# LCD.net
KiCad netlist of a schematic drawn in Altium Designer
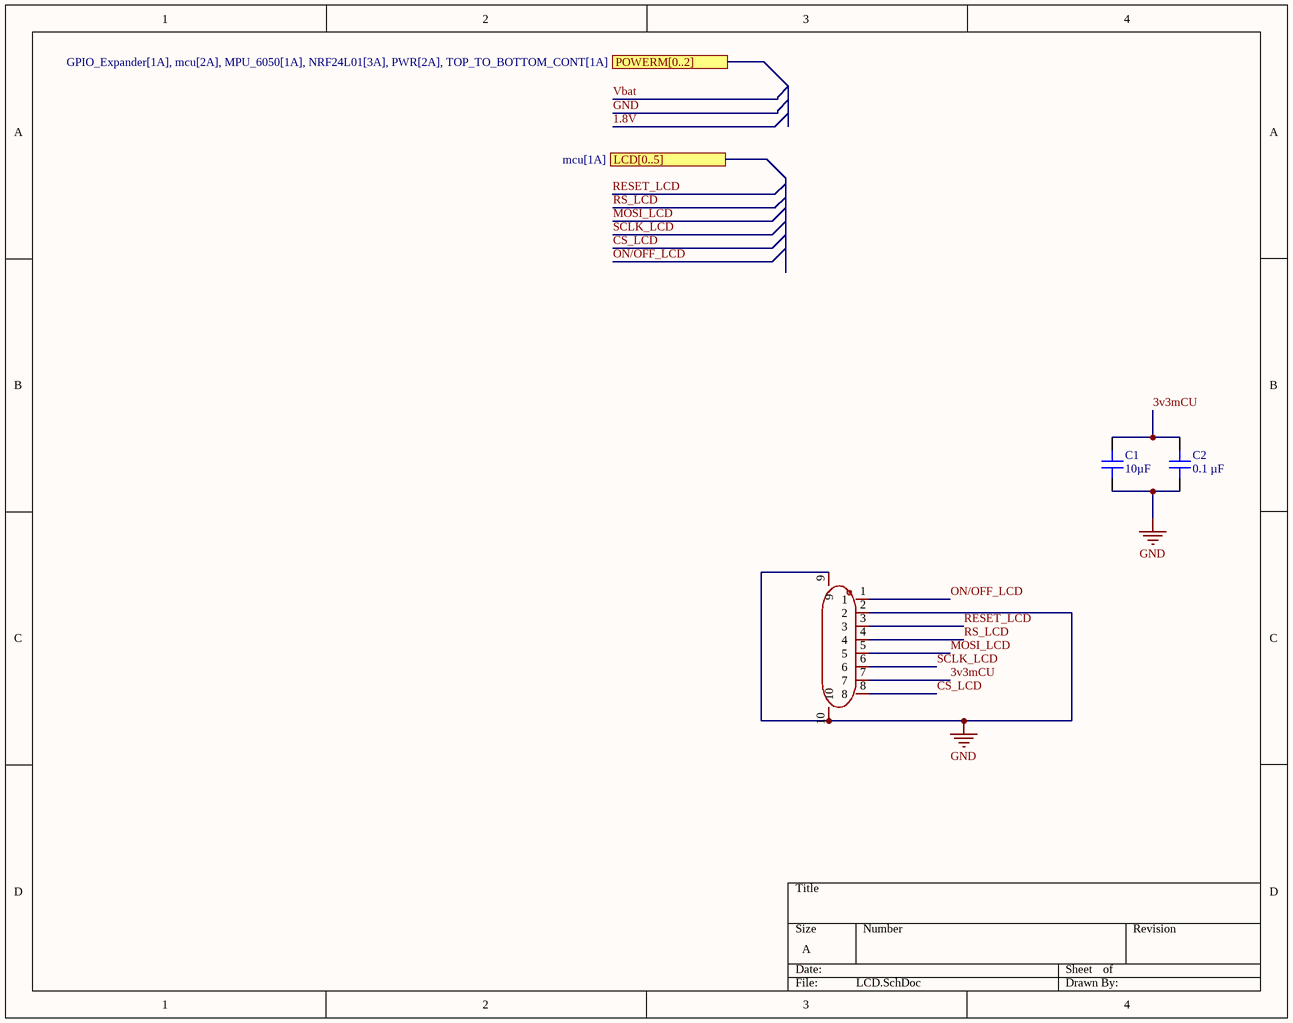
[diagram p0: LCD.SchDoc]

(export (version "E")
  (design (tool "Eeschema 10.0.6"))
  (components
    (comp (ref "C1")
      (value "~")
      (footprint "CAP 0402_1005")
      (description "CAP CER 10UF 10V X5R 0402")
      (fields
        (field (name "CAPACITANCE") "10µF")
        (field (name "JLCPCB PART #") "C307415")
        (field (name "MFR.PART #") "CL05A106MP8NUB8")
      )
      (libsource (lib "Celestial Altium Library - altium_library") (part "Capacitor"))
    )
    (comp (ref "C2")
      (value "~")
      (footprint "CAP 0402_1005")
      (description "CAP CER 0.1UF 10V X7R 0402")
      (fields
        (field (name "CAPACITANCE") "0.1 µF")
        (field (name "JLCPCB PART #") "C71687")
        (field (name "MFR.PART #") "GRM155R71A104KA01D")
      )
      (libsource (lib "Celestial Altium Library - altium_library") (part "Capacitor"))
    )
    (comp (ref "FPC1")
      (value "AFC04-S08ECA-00")
      (footprint "FPC-SMD_AFC04-S08ECA-00")
      (fields (field (name "JLCPCB PART #") "C883637") (field (name "MANUFACTURER") "JUSHUO"))
      (libsource (lib "altium-import") (part "root_0_mirrored_AFC04-S08ECA-00_"))
    )
  )
  (nets
    (net (code "11") (name "/3v3mCU") (class "Default")
      (node (ref "C1") (pin "2") (pinfunction "2_2") (pintype "passive"))
      (node (ref "C2") (pin "2") (pinfunction "2_2") (pintype "passive"))
      (node (ref "FPC1") (pin "7") (pinfunction "7_7") (pintype "passive"))
    )
    (net (code "12") (name "/CS_LCD") (class "Default")
      (node (ref "FPC1") (pin "8") (pinfunction "8_8") (pintype "passive"))
    )
    (net (code "14") (name "/MOSI_LCD") (class "Default")
      (node (ref "FPC1") (pin "5") (pinfunction "5_5") (pintype "passive"))
    )
    (net (code "15") (name "/ON{slash}OFF_LCD") (class "Default")
      (node (ref "FPC1") (pin "1") (pinfunction "1_1") (pintype "passive"))
    )
    (net (code "17") (name "/RESET_LCD") (class "Default")
      (node (ref "FPC1") (pin "3") (pinfunction "3_3") (pintype "passive"))
    )
    (net (code "18") (name "/RS_LCD") (class "Default")
      (node (ref "FPC1") (pin "4") (pinfunction "4_4") (pintype "passive"))
    )
    (net (code "19") (name "/SCLK_LCD") (class "Default")
      (node (ref "FPC1") (pin "6") (pinfunction "6_6") (pintype "passive"))
    )
    (net (code "21") (name "GND") (class "Default")
      (node (ref "C1") (pin "1") (pinfunction "1_1") (pintype "passive"))
      (node (ref "C2") (pin "1") (pinfunction "1_1") (pintype "passive"))
      (node (ref "FPC1") (pin "10") (pinfunction "10_10") (pintype "passive"))
      (node (ref "FPC1") (pin "2") (pinfunction "2_2") (pintype "passive"))
      (node (ref "FPC1") (pin "9") (pinfunction "9_9") (pintype "passive"))
    )
  )
)
